# Carte_Logique_V1.net
KiCad netlist of a schematic drawn in EasyEDA
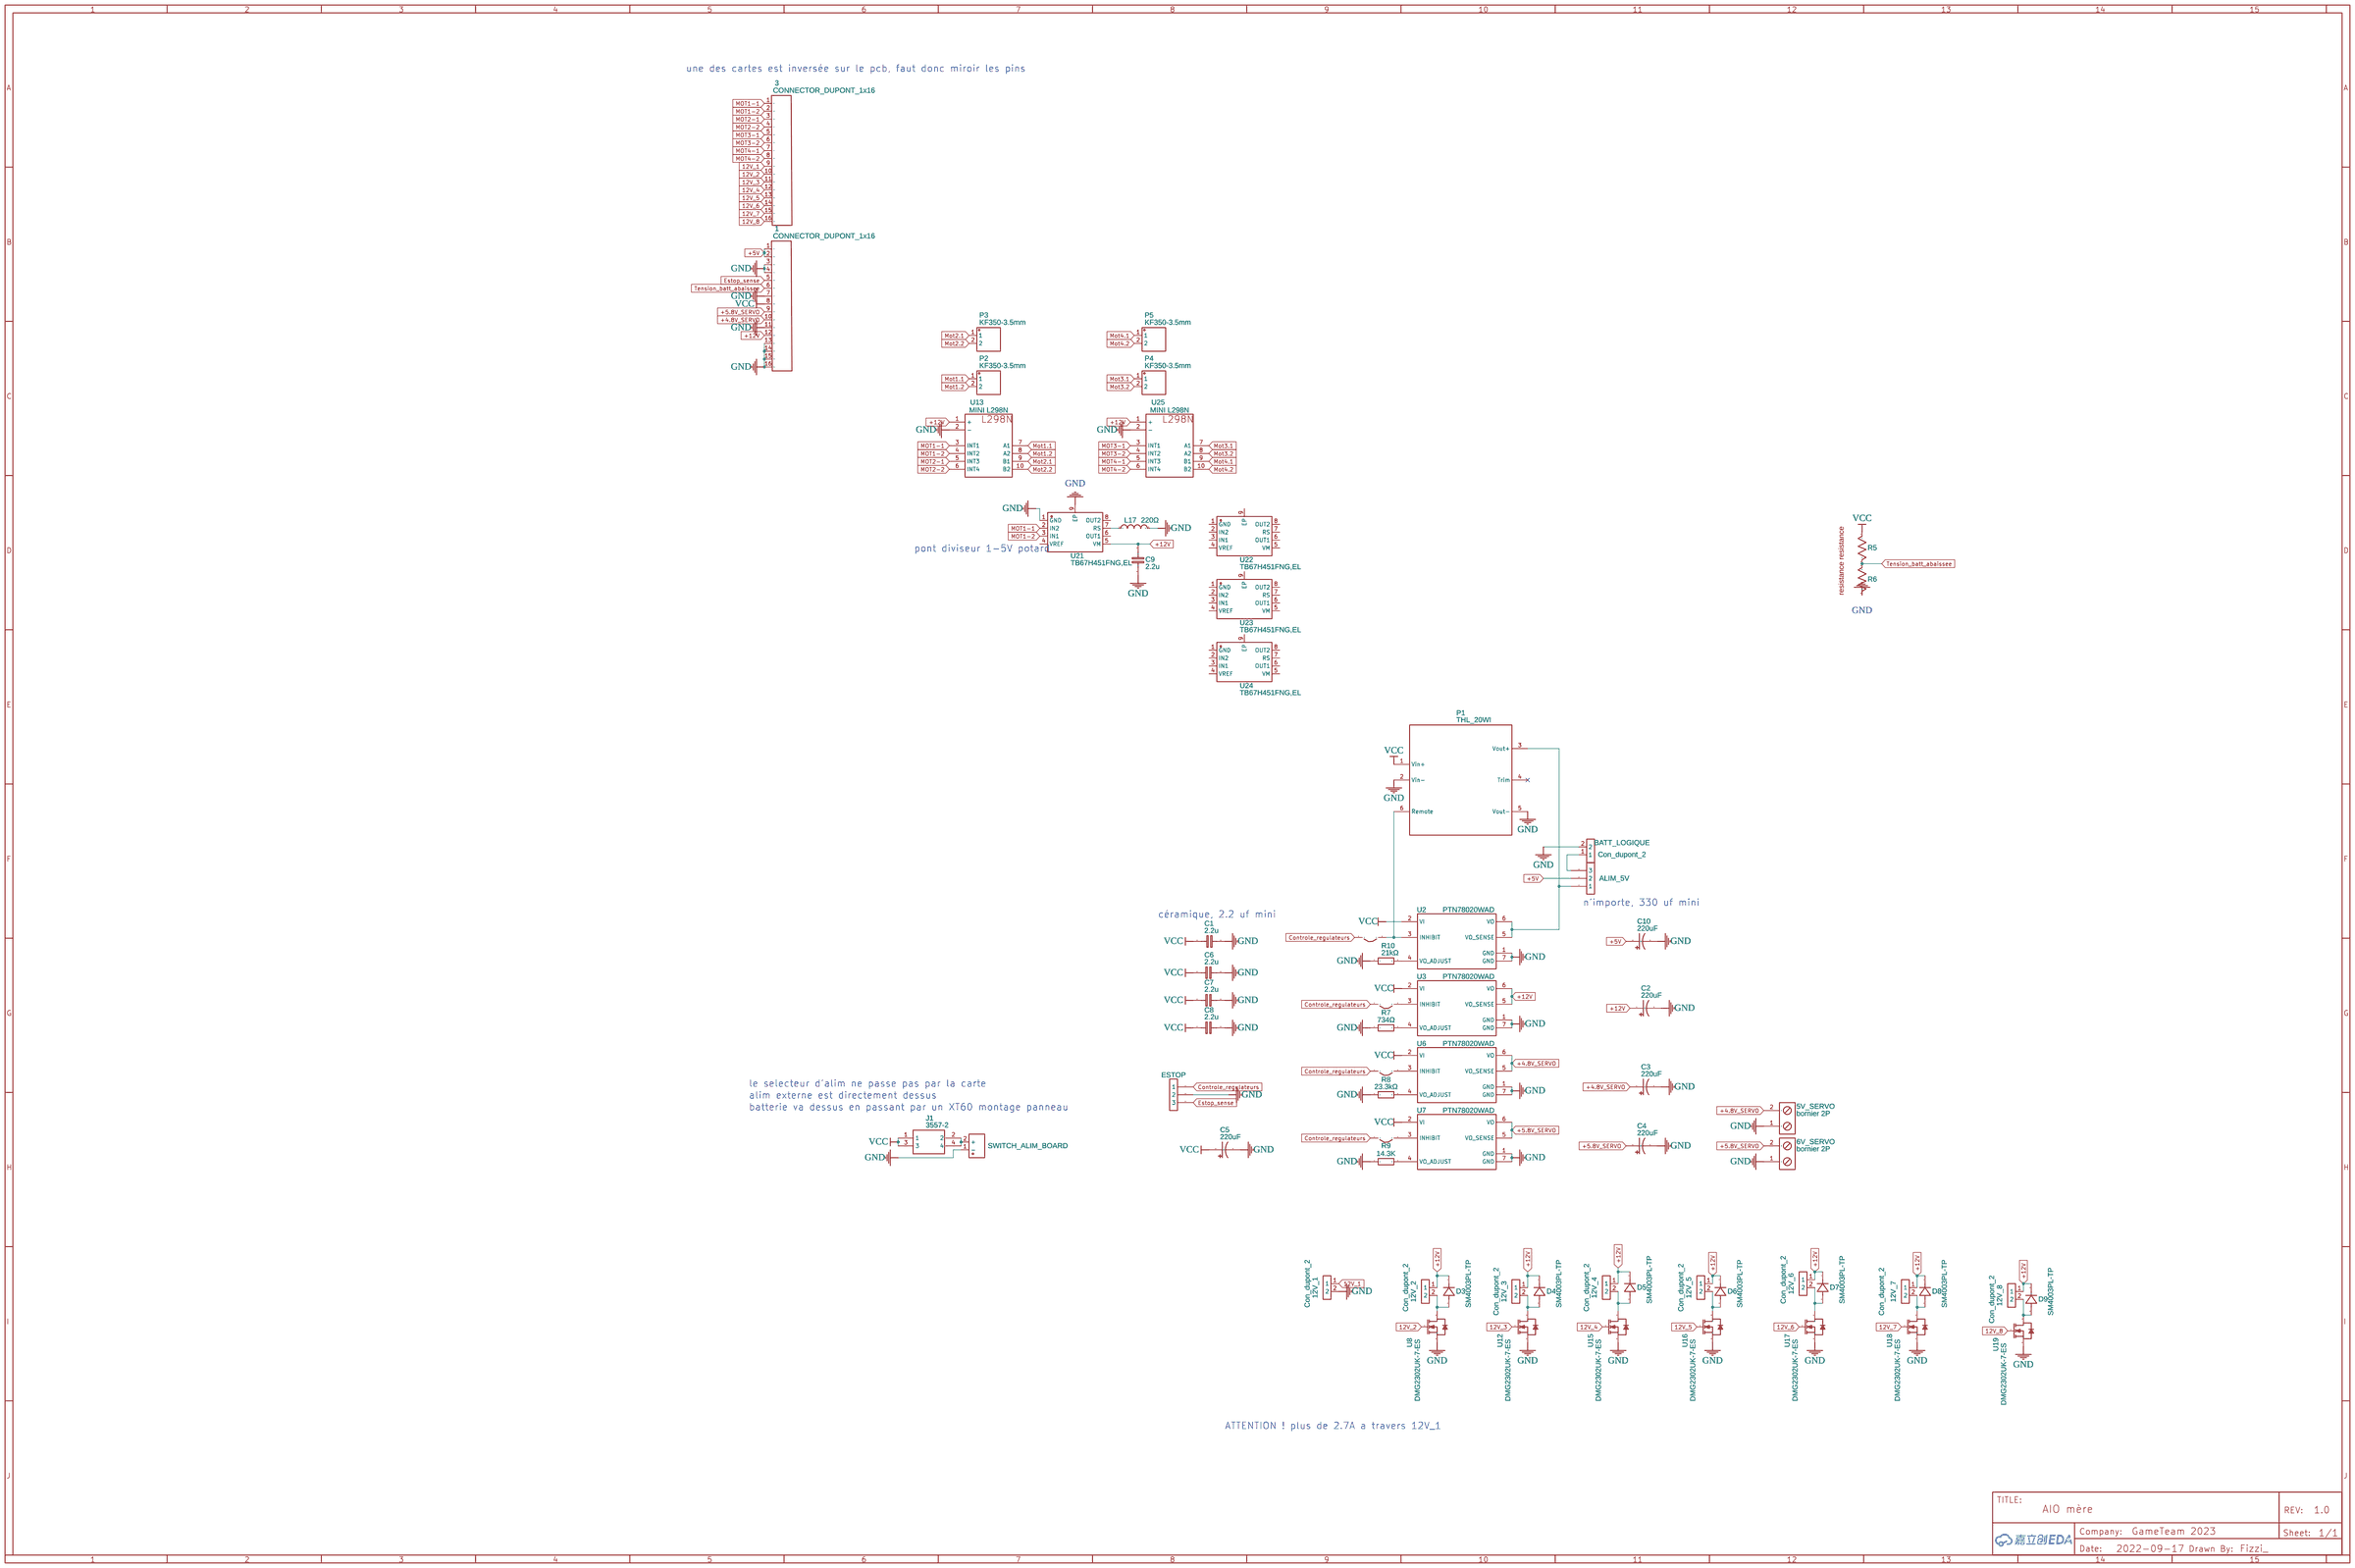
[diagram p0: schematic sheet]

(export (version "E")
  (design (tool "Eeschema 10.0.6"))
  (components
    (comp (ref "1") (value "CONNECTOR_DUPONT_1x16") (libsource (lib "") (part "CONNECTOR_DUPONT_1x16")))
    (comp (ref "3") (value "CONNECTOR_DUPONT_1x16") (libsource (lib "") (part "CONNECTOR_DUPONT_1x16")))
    (comp (ref "5V_SERVO")
      (value "bornier 2P")
      (fields (field (name "BOM_Manufacturer Part") "bornier"))
      (libsource (lib "") (part "bornier 2P"))
    )
    (comp (ref "6V_SERVO")
      (value "bornier 2P")
      (fields (field (name "BOM_Manufacturer Part") "bornier"))
      (libsource (lib "") (part "bornier 2P_1"))
    )
    (comp (ref "12V_1") (value "Con_dupont_2") (libsource (lib "") (part "Con_dupont_2")))
    (comp (ref "12V_2") (value "Con_dupont_2") (libsource (lib "") (part "Con_dupont_2")))
    (comp (ref "12V_3") (value "Con_dupont_2") (libsource (lib "") (part "Con_dupont_2")))
    (comp (ref "12V_4") (value "Con_dupont_2") (libsource (lib "") (part "Con_dupont_2")))
    (comp (ref "12V_5") (value "Con_dupont_2") (libsource (lib "") (part "Con_dupont_2")))
    (comp (ref "12V_6") (value "Con_dupont_2") (libsource (lib "") (part "Con_dupont_2")))
    (comp (ref "12V_7") (value "Con_dupont_2") (libsource (lib "") (part "Con_dupont_2")))
    (comp (ref "12V_8") (value "Con_dupont_2") (libsource (lib "") (part "Con_dupont_2")))
    (comp (ref "ALIM_5V") (value "Dupont 3Pin") (libsource (lib "") (part "Dupont 3Pin_1")))
    (comp (ref "BATT_LOGIQUE") (value "Con_dupont_2") (libsource (lib "") (part "Con_dupont_2_1")))
    (comp (ref "C1") (value "2.2u") (libsource (lib "") (part "C_0805_EU_2")))
    (comp (ref "C2")
      (value "220uF")
      (fields
        (field (name "BOM_Manufacturer Part") "EEEFK1H221P")
        (field (name "BOM_Supplier Part") "C178549")
      )
      (libsource (lib "") (part "EEEFK1H221P"))
    )
    (comp (ref "C3")
      (value "220uF")
      (fields
        (field (name "BOM_Manufacturer Part") "EEEFK1H221P")
        (field (name "BOM_Supplier Part") "C178549")
      )
      (libsource (lib "") (part "EEEFK1H221P"))
    )
    (comp (ref "C4")
      (value "220uF")
      (fields
        (field (name "BOM_Manufacturer Part") "EEEFK1H221P")
        (field (name "BOM_Supplier Part") "C178549")
      )
      (libsource (lib "") (part "EEEFK1H221P"))
    )
    (comp (ref "C5")
      (value "220uF")
      (fields
        (field (name "BOM_Manufacturer Part") "EEEFK1H221P")
        (field (name "BOM_Supplier Part") "C178549")
      )
      (libsource (lib "") (part "EEEFK1H221P"))
    )
    (comp (ref "C6") (value "2.2u") (libsource (lib "") (part "C_0805_EU")))
    (comp (ref "C7") (value "2.2u") (libsource (lib "") (part "C_0805_EU")))
    (comp (ref "C8") (value "2.2u") (libsource (lib "") (part "C_0805_EU")))
    (comp (ref "C9") (value "2.2u") (libsource (lib "") (part "C_0805_EU_1")))
    (comp (ref "C10")
      (value "220uF")
      (fields
        (field (name "BOM_Manufacturer Part") "EEEFK1H221P")
        (field (name "BOM_Supplier Part") "C178549")
      )
      (libsource (lib "") (part "EEEFK1H221P"))
    )
    (comp (ref "D3")
      (value "SM4003PL-TP")
      (fields (field (name "BOM_Supplier Part") "C725472"))
      (libsource (lib "") (part "SM4003PL-TP"))
    )
    (comp (ref "D4")
      (value "SM4003PL-TP")
      (fields (field (name "BOM_Supplier Part") "C725472"))
      (libsource (lib "") (part "SM4003PL-TP"))
    )
    (comp (ref "D5")
      (value "SM4003PL-TP")
      (fields (field (name "BOM_Supplier Part") "C725472"))
      (libsource (lib "") (part "SM4003PL-TP"))
    )
    (comp (ref "D6")
      (value "SM4003PL-TP")
      (fields (field (name "BOM_Supplier Part") "C725472"))
      (libsource (lib "") (part "SM4003PL-TP"))
    )
    (comp (ref "D7")
      (value "SM4003PL-TP")
      (fields (field (name "BOM_Supplier Part") "C725472"))
      (libsource (lib "") (part "SM4003PL-TP"))
    )
    (comp (ref "D8")
      (value "SM4003PL-TP")
      (fields (field (name "BOM_Supplier Part") "C725472"))
      (libsource (lib "") (part "SM4003PL-TP"))
    )
    (comp (ref "D9")
      (value "SM4003PL-TP")
      (fields (field (name "BOM_Supplier Part") "C725472"))
      (libsource (lib "") (part "SM4003PL-TP"))
    )
    (comp (ref "ESTOP") (value "Dupont 3Pin") (libsource (lib "") (part "Dupont 3Pin")))
    (comp (ref "J1") (value "3557-2") (libsource (lib "") (part "3557-2")))
    (comp (ref "JP8") (value "Jumper") (libsource (lib "") (part "Jumper Solder Bridge")))
    (comp (ref "JP9") (value "Jumper") (libsource (lib "") (part "Jumper Solder Bridge")))
    (comp (ref "JP10") (value "Jumper") (libsource (lib "") (part "Jumper Solder Bridge")))
    (comp (ref "JP11") (value "Jumper") (libsource (lib "") (part "Jumper Solder Bridge")))
    (comp (ref "L17")
      (value "220Ω")
      (fields
        (field (name "BOM_Manufacturer Part") "BLM18SG221TN1D")
        (field (name "BOM_Supplier Part") "C88988")
      )
      (libsource (lib "") (part "BLM18SG221TN1D"))
    )
    (comp (ref "P1") (value "THL_20WI") (libsource (lib "") (part "THL_20WI")))
    (comp (ref "P2")
      (value "KF350-3.5mm")
      (fields
        (field (name "BOM_Manufacturer Part") "WJ2EDGVC-5.08-2P")
        (field (name "BOM_Supplier Part") "C8445")
      )
      (libsource (lib "") (part "KF350-3.5mm"))
    )
    (comp (ref "P3")
      (value "KF350-3.5mm")
      (fields
        (field (name "BOM_Manufacturer Part") "WJ2EDGVC-5.08-2P")
        (field (name "BOM_Supplier Part") "C8445")
      )
      (libsource (lib "") (part "KF350-3.5mm"))
    )
    (comp (ref "P4")
      (value "KF350-3.5mm")
      (fields
        (field (name "BOM_Manufacturer Part") "WJ2EDGVC-5.08-2P")
        (field (name "BOM_Supplier Part") "C8445")
      )
      (libsource (lib "") (part "KF350-3.5mm"))
    )
    (comp (ref "P5")
      (value "KF350-3.5mm")
      (fields
        (field (name "BOM_Manufacturer Part") "WJ2EDGVC-5.08-2P")
        (field (name "BOM_Supplier Part") "C8445")
      )
      (libsource (lib "") (part "KF350-3.5mm"))
    )
    (comp (ref "R5") (value "1K") (libsource (lib "") (part "TROUGH HOLE RESISTOR 12MM")))
    (comp (ref "R6") (value "1K") (libsource (lib "") (part "TROUGH HOLE RESISTOR 12MM_1")))
    (comp (ref "R7")
      (value "734Ω")
      (fields
        (field (name "BOM_Manufacturer Part") "TR0603D383KP0515")
        (field (name "BOM_Supplier Part") "C153382")
      )
      (libsource (lib "") (part "TR0603D383KP0515"))
    )
    (comp (ref "R8")
      (value "23.3kΩ")
      (fields
        (field (name "BOM_Manufacturer Part") "0603WAF2322T5E")
        (field (name "BOM_Supplier Part") "C23346")
      )
      (libsource (lib "") (part "0603WAF2322T5E"))
    )
    (comp (ref "R9")
      (value "14.3K")
      (fields
        (field (name "BOM_Manufacturer Part") "AC0603FR-0714K3L")
        (field (name "BOM_Supplier Part") "C227592")
      )
      (libsource (lib "") (part "AC0603FR-0714K3L"))
    )
    (comp (ref "R10")
      (value "21kΩ")
      (fields
        (field (name "BOM_Manufacturer Part") "HPCR0603F21K0K9")
        (field (name "BOM_Supplier Part") "C365119")
      )
      (libsource (lib "") (part "HPCR0603F21K0K9"))
    )
    (comp (ref "SWITCH_ALIM_BOARD")
      (value "XT60-M")
      (fields
        (field (name "BOM_Manufacturer Part") "XT60UPB-M")
        (field (name "BOM_Supplier Part") "C2918078")
      )
      (libsource (lib "") (part "XT60-M"))
    )
    (comp (ref "U2") (value "PTN78020WAD") (libsource (lib "") (part "PTN78020WAD")))
    (comp (ref "U3") (value "PTN78020WAD") (libsource (lib "") (part "PTN78020WAD")))
    (comp (ref "U6") (value "PTN78020WAD") (libsource (lib "") (part "PTN78020WAD")))
    (comp (ref "U7") (value "PTN78020WAD") (libsource (lib "") (part "PTN78020WAD")))
    (comp (ref "U8")
      (value "DMG2302UK-7-ES")
      (fields (field (name "BOM_Supplier Part") "C5224188"))
      (libsource (lib "") (part "DMG2302UK-7-ES"))
    )
    (comp (ref "U12")
      (value "DMG2302UK-7-ES")
      (fields (field (name "BOM_Supplier Part") "C5224188"))
      (libsource (lib "") (part "DMG2302UK-7-ES"))
    )
    (comp (ref "U13") (value "MINI L298N") (libsource (lib "") (part "MINI L298N")))
    (comp (ref "U15")
      (value "DMG2302UK-7-ES")
      (fields (field (name "BOM_Supplier Part") "C5224188"))
      (libsource (lib "") (part "DMG2302UK-7-ES"))
    )
    (comp (ref "U16")
      (value "DMG2302UK-7-ES")
      (fields (field (name "BOM_Supplier Part") "C5224188"))
      (libsource (lib "") (part "DMG2302UK-7-ES"))
    )
    (comp (ref "U17")
      (value "DMG2302UK-7-ES")
      (fields (field (name "BOM_Supplier Part") "C5224188"))
      (libsource (lib "") (part "DMG2302UK-7-ES"))
    )
    (comp (ref "U18")
      (value "DMG2302UK-7-ES")
      (fields (field (name "BOM_Supplier Part") "C5224188"))
      (libsource (lib "") (part "DMG2302UK-7-ES"))
    )
    (comp (ref "U19")
      (value "DMG2302UK-7-ES")
      (fields (field (name "BOM_Supplier Part") "C5224188"))
      (libsource (lib "") (part "DMG2302UK-7-ES"))
    )
    (comp (ref "U21")
      (value "TB67H451FNG,EL")
      (fields (field (name "BOM_Supplier Part") "C1858375"))
      (libsource (lib "") (part "TB67H451FNG,EL"))
    )
    (comp (ref "U22")
      (value "TB67H451FNG,EL")
      (fields (field (name "BOM_Supplier Part") "C1858375"))
      (libsource (lib "") (part "TB67H451FNG,EL"))
    )
    (comp (ref "U23")
      (value "TB67H451FNG,EL")
      (fields (field (name "BOM_Supplier Part") "C1858375"))
      (libsource (lib "") (part "TB67H451FNG,EL"))
    )
    (comp (ref "U24")
      (value "TB67H451FNG,EL")
      (fields (field (name "BOM_Supplier Part") "C1858375"))
      (libsource (lib "") (part "TB67H451FNG,EL"))
    )
    (comp (ref "U25") (value "MINI L298N") (libsource (lib "") (part "MINI L298N")))
  )
  (nets
    (net (code "1") (name "+4.8V_SERVO") (class "Default")
      (node (ref "1") (pin "10") (pinfunction "10_10") (pintype "bidirectional"))
      (node (ref "5V_SERVO") (pin "2") (pinfunction "2_2") (pintype "unspecified"))
      (node (ref "C3") (pin "1") (pinfunction "1_1") (pintype "unspecified"))
      (node (ref "U6") (pin "5") (pinfunction "VO_SENSE_5") (pintype "unspecified"))
      (node (ref "U6") (pin "6") (pinfunction "VO_6") (pintype "passive"))
    )
    (net (code "2") (name "+5.8V_SERVO") (class "Default")
      (node (ref "1") (pin "9") (pinfunction "9_9") (pintype "bidirectional"))
      (node (ref "6V_SERVO") (pin "2") (pinfunction "2_2") (pintype "unspecified"))
      (node (ref "C4") (pin "1") (pinfunction "1_1") (pintype "unspecified"))
      (node (ref "U7") (pin "5") (pinfunction "VO_SENSE_5") (pintype "unspecified"))
      (node (ref "U7") (pin "6") (pinfunction "VO_6") (pintype "passive"))
    )
    (net (code "3") (name "+5V") (class "Default")
      (node (ref "1") (pin "1") (pinfunction "1_1") (pintype "bidirectional"))
      (node (ref "1") (pin "2") (pinfunction "2_2") (pintype "bidirectional"))
      (node (ref "ALIM_5V") (pin "2") (pinfunction "2_2") (pintype "unspecified"))
      (node (ref "C10") (pin "1") (pinfunction "1_1") (pintype "unspecified"))
    )
    (net (code "4") (name "+12V") (class "Default")
      (node (ref "1") (pin "12") (pinfunction "12_12") (pintype "bidirectional"))
      (node (ref "12V_2") (pin "1") (pinfunction "1_1") (pintype "unspecified"))
      (node (ref "12V_3") (pin "1") (pinfunction "1_1") (pintype "unspecified"))
      (node (ref "12V_4") (pin "1") (pinfunction "1_1") (pintype "unspecified"))
      (node (ref "12V_5") (pin "1") (pinfunction "1_1") (pintype "unspecified"))
      (node (ref "12V_6") (pin "1") (pinfunction "1_1") (pintype "unspecified"))
      (node (ref "12V_7") (pin "1") (pinfunction "1_1") (pintype "unspecified"))
      (node (ref "12V_8") (pin "1") (pinfunction "1_1") (pintype "unspecified"))
      (node (ref "C2") (pin "1") (pinfunction "1_1") (pintype "unspecified"))
      (node (ref "C9") (pin "2") (pinfunction "2_2") (pintype "unspecified"))
      (node (ref "D3") (pin "1") (pinfunction "K_1") (pintype "unspecified"))
      (node (ref "D4") (pin "1") (pinfunction "K_1") (pintype "unspecified"))
      (node (ref "D5") (pin "1") (pinfunction "K_1") (pintype "unspecified"))
      (node (ref "D6") (pin "1") (pinfunction "K_1") (pintype "unspecified"))
      (node (ref "D7") (pin "1") (pinfunction "K_1") (pintype "unspecified"))
      (node (ref "D8") (pin "1") (pinfunction "K_1") (pintype "unspecified"))
      (node (ref "D9") (pin "1") (pinfunction "K_1") (pintype "unspecified"))
      (node (ref "U13") (pin "1") (pinfunction "+_1") (pintype "unspecified"))
      (node (ref "U21") (pin "5") (pinfunction "VM_5") (pintype "unspecified"))
      (node (ref "U25") (pin "1") (pinfunction "+_1") (pintype "unspecified"))
      (node (ref "U3") (pin "5") (pinfunction "VO_SENSE_5") (pintype "unspecified"))
      (node (ref "U3") (pin "6") (pinfunction "VO_6") (pintype "passive"))
    )
    (net (code "5") (name "12V_1") (class "Default")
      (node (ref "12V_1") (pin "1") (pinfunction "1_1") (pintype "unspecified"))
      (node (ref "3") (pin "9") (pinfunction "9_9") (pintype "bidirectional"))
    )
    (net (code "6") (name "12V_2") (class "Default")
      (node (ref "3") (pin "10") (pinfunction "10_10") (pintype "bidirectional"))
      (node (ref "U8") (pin "1") (pinfunction "G_1") (pintype "unspecified"))
    )
    (net (code "7") (name "12V_3") (class "Default")
      (node (ref "3") (pin "11") (pinfunction "11_11") (pintype "bidirectional"))
      (node (ref "U12") (pin "1") (pinfunction "G_1") (pintype "unspecified"))
    )
    (net (code "8") (name "12V_4") (class "Default")
      (node (ref "3") (pin "12") (pinfunction "12_12") (pintype "bidirectional"))
      (node (ref "U15") (pin "1") (pinfunction "G_1") (pintype "unspecified"))
    )
    (net (code "9") (name "12V_5") (class "Default")
      (node (ref "3") (pin "13") (pinfunction "13_13") (pintype "bidirectional"))
      (node (ref "U16") (pin "1") (pinfunction "G_1") (pintype "unspecified"))
    )
    (net (code "10") (name "12V_6") (class "Default")
      (node (ref "3") (pin "14") (pinfunction "14_14") (pintype "bidirectional"))
      (node (ref "U17") (pin "1") (pinfunction "G_1") (pintype "unspecified"))
    )
    (net (code "11") (name "12V_7") (class "Default")
      (node (ref "3") (pin "15") (pinfunction "15_15") (pintype "bidirectional"))
      (node (ref "U18") (pin "1") (pinfunction "G_1") (pintype "unspecified"))
    )
    (net (code "12") (name "12V_8") (class "Default")
      (node (ref "3") (pin "16") (pinfunction "16_16") (pintype "bidirectional"))
      (node (ref "U19") (pin "1") (pinfunction "G_1") (pintype "unspecified"))
    )
    (net (code "13") (name "Controle_regulateurs") (class "Default")
      (node (ref "ESTOP") (pin "1") (pinfunction "1_1") (pintype "unspecified"))
      (node (ref "JP10") (pin "1") (pinfunction "1_1") (pintype "input"))
      (node (ref "JP11") (pin "1") (pinfunction "1_1") (pintype "input"))
      (node (ref "JP8") (pin "1") (pinfunction "1_1") (pintype "input"))
      (node (ref "JP9") (pin "1") (pinfunction "1_1") (pintype "input"))
    )
    (net (code "14") (name "Estop_sense") (class "Default")
      (node (ref "1") (pin "5") (pinfunction "5_5") (pintype "bidirectional"))
      (node (ref "ESTOP") (pin "3") (pinfunction "3_3") (pintype "unspecified"))
    )
    (net (code "15") (name "GND") (class "Default")
      (node (ref "1") (pin "11") (pinfunction "11_11") (pintype "bidirectional"))
      (node (ref "1") (pin "13") (pinfunction "13_13") (pintype "bidirectional"))
      (node (ref "1") (pin "14") (pinfunction "14_14") (pintype "bidirectional"))
      (node (ref "1") (pin "15") (pinfunction "15_15") (pintype "bidirectional"))
      (node (ref "1") (pin "16") (pinfunction "16_16") (pintype "bidirectional"))
      (node (ref "1") (pin "3") (pinfunction "3_3") (pintype "bidirectional"))
      (node (ref "1") (pin "4") (pinfunction "4_4") (pintype "bidirectional"))
      (node (ref "1") (pin "7") (pinfunction "7_7") (pintype "bidirectional"))
      (node (ref "12V_1") (pin "2") (pinfunction "2_2") (pintype "unspecified"))
      (node (ref "5V_SERVO") (pin "1") (pinfunction "1_1") (pintype "unspecified"))
      (node (ref "6V_SERVO") (pin "1") (pinfunction "1_1") (pintype "unspecified"))
      (node (ref "BATT_LOGIQUE") (pin "2") (pinfunction "2_2") (pintype "unspecified"))
      (node (ref "C1") (pin "1") (pinfunction "1_1") (pintype "unspecified"))
      (node (ref "C10") (pin "2") (pinfunction "2_2") (pintype "unspecified"))
      (node (ref "C2") (pin "2") (pinfunction "2_2") (pintype "unspecified"))
      (node (ref "C3") (pin "2") (pinfunction "2_2") (pintype "unspecified"))
      (node (ref "C4") (pin "2") (pinfunction "2_2") (pintype "unspecified"))
      (node (ref "C5") (pin "2") (pinfunction "2_2") (pintype "unspecified"))
      (node (ref "C6") (pin "2") (pinfunction "2_2") (pintype "unspecified"))
      (node (ref "C7") (pin "2") (pinfunction "2_2") (pintype "unspecified"))
      (node (ref "C8") (pin "2") (pinfunction "2_2") (pintype "unspecified"))
      (node (ref "C9") (pin "1") (pinfunction "1_1") (pintype "unspecified"))
      (node (ref "ESTOP") (pin "2") (pinfunction "2_2") (pintype "unspecified"))
      (node (ref "L17") (pin "2") (pinfunction "2_2") (pintype "unspecified"))
      (node (ref "P1") (pin "2") (pinfunction "Vin-_2") (pintype "unspecified"))
      (node (ref "P1") (pin "5") (pinfunction "Vout-_5") (pintype "unspecified"))
      (node (ref "R10") (pin "1") (pinfunction "1_1") (pintype "unspecified"))
      (node (ref "R6") (pin "2") (pinfunction "2_2") (pintype "unspecified"))
      (node (ref "R7") (pin "1") (pinfunction "1_1") (pintype "unspecified"))
      (node (ref "R8") (pin "1") (pinfunction "1_1") (pintype "input"))
      (node (ref "R9") (pin "1") (pinfunction "1_1") (pintype "unspecified"))
      (node (ref "SWITCH_ALIM_BOARD") (pin "1") (pinfunction "-_1") (pintype "unspecified"))
      (node (ref "U12") (pin "2") (pinfunction "S_2") (pintype "unspecified"))
      (node (ref "U13") (pin "2") (pinfunction "-_2") (pintype "unspecified"))
      (node (ref "U15") (pin "2") (pinfunction "S_2") (pintype "unspecified"))
      (node (ref "U16") (pin "2") (pinfunction "S_2") (pintype "unspecified"))
      (node (ref "U17") (pin "2") (pinfunction "S_2") (pintype "unspecified"))
      (node (ref "U18") (pin "2") (pinfunction "S_2") (pintype "unspecified"))
      (node (ref "U19") (pin "2") (pinfunction "S_2") (pintype "unspecified"))
      (node (ref "U2") (pin "1") (pinfunction "GND_1") (pintype "passive"))
      (node (ref "U2") (pin "7") (pinfunction "GND_7") (pintype "passive"))
      (node (ref "U21") (pin "1") (pinfunction "GND_1") (pintype "unspecified"))
      (node (ref "U21") (pin "9") (pinfunction "EP_9") (pintype "unspecified"))
      (node (ref "U25") (pin "2") (pinfunction "-_2") (pintype "unspecified"))
      (node (ref "U3") (pin "1") (pinfunction "GND_1") (pintype "passive"))
      (node (ref "U3") (pin "7") (pinfunction "GND_7") (pintype "passive"))
      (node (ref "U6") (pin "1") (pinfunction "GND_1") (pintype "passive"))
      (node (ref "U6") (pin "7") (pinfunction "GND_7") (pintype "passive"))
      (node (ref "U7") (pin "1") (pinfunction "GND_1") (pintype "passive"))
      (node (ref "U7") (pin "7") (pinfunction "GND_7") (pintype "passive"))
      (node (ref "U8") (pin "2") (pinfunction "S_2") (pintype "unspecified"))
    )
    (net (code "16") (name "MOT1-1") (class "Default")
      (node (ref "3") (pin "1") (pinfunction "1_1") (pintype "bidirectional"))
      (node (ref "U13") (pin "3") (pinfunction "INT1_3") (pintype "unspecified"))
      (node (ref "U21") (pin "2") (pinfunction "IN2_2") (pintype "unspecified"))
    )
    (net (code "17") (name "MOT1-2") (class "Default")
      (node (ref "3") (pin "2") (pinfunction "2_2") (pintype "bidirectional"))
      (node (ref "U13") (pin "4") (pinfunction "INT2_4") (pintype "unspecified"))
      (node (ref "U21") (pin "3") (pinfunction "IN1_3") (pintype "unspecified"))
    )
    (net (code "18") (name "MOT2-1") (class "Default")
      (node (ref "3") (pin "3") (pinfunction "3_3") (pintype "bidirectional"))
      (node (ref "U13") (pin "5") (pinfunction "INT3_5") (pintype "unspecified"))
    )
    (net (code "19") (name "MOT2-2") (class "Default")
      (node (ref "3") (pin "4") (pinfunction "4_4") (pintype "bidirectional"))
      (node (ref "U13") (pin "6") (pinfunction "INT4_6") (pintype "unspecified"))
    )
    (net (code "20") (name "MOT3-1") (class "Default")
      (node (ref "3") (pin "5") (pinfunction "5_5") (pintype "bidirectional"))
      (node (ref "U25") (pin "3") (pinfunction "INT1_3") (pintype "unspecified"))
    )
    (net (code "21") (name "MOT3-2") (class "Default")
      (node (ref "3") (pin "6") (pinfunction "6_6") (pintype "bidirectional"))
      (node (ref "U25") (pin "4") (pinfunction "INT2_4") (pintype "unspecified"))
    )
    (net (code "22") (name "MOT4-1") (class "Default")
      (node (ref "3") (pin "7") (pinfunction "7_7") (pintype "bidirectional"))
      (node (ref "U25") (pin "5") (pinfunction "INT3_5") (pintype "unspecified"))
    )
    (net (code "23") (name "MOT4-2") (class "Default")
      (node (ref "3") (pin "8") (pinfunction "8_8") (pintype "bidirectional"))
      (node (ref "U25") (pin "6") (pinfunction "INT4_6") (pintype "unspecified"))
    )
    (net (code "24") (name "Mot1.1") (class "Default")
      (node (ref "P2") (pin "1") (pinfunction "1_1") (pintype "unspecified"))
      (node (ref "U13") (pin "7") (pinfunction "A1_7") (pintype "unspecified"))
    )
    (net (code "25") (name "Mot1.2") (class "Default")
      (node (ref "P2") (pin "2") (pinfunction "2_2") (pintype "unspecified"))
      (node (ref "U13") (pin "8") (pinfunction "A2_8") (pintype "unspecified"))
    )
    (net (code "26") (name "Mot2.1") (class "Default")
      (node (ref "P3") (pin "1") (pinfunction "1_1") (pintype "unspecified"))
      (node (ref "U13") (pin "9") (pinfunction "B1_9") (pintype "unspecified"))
    )
    (net (code "27") (name "Mot2.2") (class "Default")
      (node (ref "P3") (pin "2") (pinfunction "2_2") (pintype "unspecified"))
      (node (ref "U13") (pin "10") (pinfunction "B2_10") (pintype "unspecified"))
    )
    (net (code "28") (name "Mot3.1") (class "Default")
      (node (ref "P4") (pin "1") (pinfunction "1_1") (pintype "unspecified"))
      (node (ref "U25") (pin "7") (pinfunction "A1_7") (pintype "unspecified"))
    )
    (net (code "29") (name "Mot3.2") (class "Default")
      (node (ref "P4") (pin "2") (pinfunction "2_2") (pintype "unspecified"))
      (node (ref "U25") (pin "8") (pinfunction "A2_8") (pintype "unspecified"))
    )
    (net (code "30") (name "Mot4.1") (class "Default")
      (node (ref "P5") (pin "1") (pinfunction "1_1") (pintype "unspecified"))
      (node (ref "U25") (pin "9") (pinfunction "B1_9") (pintype "unspecified"))
    )
    (net (code "31") (name "Mot4.2") (class "Default")
      (node (ref "P5") (pin "2") (pinfunction "2_2") (pintype "unspecified"))
      (node (ref "U25") (pin "10") (pinfunction "B2_10") (pintype "unspecified"))
    )
    (net (code "32") (name "Net-(ALIM_5V-Pad3)") (class "Default")
      (node (ref "ALIM_5V") (pin "3") (pinfunction "3_3") (pintype "unspecified"))
      (node (ref "BATT_LOGIQUE") (pin "1") (pinfunction "1_1") (pintype "unspecified"))
    )
    (net (code "33") (name "Net-(D3-A)") (class "Default")
      (node (ref "12V_2") (pin "2") (pinfunction "2_2") (pintype "unspecified"))
      (node (ref "D3") (pin "2") (pinfunction "A_2") (pintype "unspecified"))
      (node (ref "U8") (pin "3") (pinfunction "D_3") (pintype "unspecified"))
    )
    (net (code "34") (name "Net-(D4-A)") (class "Default")
      (node (ref "12V_3") (pin "2") (pinfunction "2_2") (pintype "unspecified"))
      (node (ref "D4") (pin "2") (pinfunction "A_2") (pintype "unspecified"))
      (node (ref "U12") (pin "3") (pinfunction "D_3") (pintype "unspecified"))
    )
    (net (code "35") (name "Net-(D5-A)") (class "Default")
      (node (ref "12V_4") (pin "2") (pinfunction "2_2") (pintype "unspecified"))
      (node (ref "D5") (pin "2") (pinfunction "A_2") (pintype "unspecified"))
      (node (ref "U15") (pin "3") (pinfunction "D_3") (pintype "unspecified"))
    )
    (net (code "36") (name "Net-(D6-A)") (class "Default")
      (node (ref "12V_5") (pin "2") (pinfunction "2_2") (pintype "unspecified"))
      (node (ref "D6") (pin "2") (pinfunction "A_2") (pintype "unspecified"))
      (node (ref "U16") (pin "3") (pinfunction "D_3") (pintype "unspecified"))
    )
    (net (code "37") (name "Net-(D7-A)") (class "Default")
      (node (ref "12V_6") (pin "2") (pinfunction "2_2") (pintype "unspecified"))
      (node (ref "D7") (pin "2") (pinfunction "A_2") (pintype "unspecified"))
      (node (ref "U17") (pin "3") (pinfunction "D_3") (pintype "unspecified"))
    )
    (net (code "38") (name "Net-(D8-A)") (class "Default")
      (node (ref "12V_7") (pin "2") (pinfunction "2_2") (pintype "unspecified"))
      (node (ref "D8") (pin "2") (pinfunction "A_2") (pintype "unspecified"))
      (node (ref "U18") (pin "3") (pinfunction "D_3") (pintype "unspecified"))
    )
    (net (code "39") (name "Net-(D9-A)") (class "Default")
      (node (ref "12V_8") (pin "2") (pinfunction "2_2") (pintype "unspecified"))
      (node (ref "D9") (pin "2") (pinfunction "A_2") (pintype "unspecified"))
      (node (ref "U19") (pin "3") (pinfunction "D_3") (pintype "unspecified"))
    )
    (net (code "40") (name "Net-(P1-Remote)") (class "Default")
      (node (ref "JP8") (pin "2") (pinfunction "2_2") (pintype "input"))
      (node (ref "P1") (pin "6") (pinfunction "Remote_6") (pintype "unspecified"))
      (node (ref "U2") (pin "3") (pinfunction "INHIBIT_3") (pintype "unspecified"))
    )
    (net (code "41") (name "Net-(P1-Vout+)") (class "Default")
      (node (ref "ALIM_5V") (pin "1") (pinfunction "1_1") (pintype "unspecified"))
      (node (ref "P1") (pin "3") (pinfunction "Vout+_3") (pintype "unspecified"))
      (node (ref "U2") (pin "5") (pinfunction "VO_SENSE_5") (pintype "unspecified"))
      (node (ref "U2") (pin "6") (pinfunction "VO_6") (pintype "passive"))
    )
    (net (code "42") (name "Net-(SWITCH_ALIM_BOARD-+)") (class "Default")
      (node (ref "J1") (pin "2") (pinfunction "2_2") (pintype "bidirectional"))
      (node (ref "J1") (pin "4") (pinfunction "4_4") (pintype "bidirectional"))
      (node (ref "SWITCH_ALIM_BOARD") (pin "2") (pinfunction "+_2") (pintype "unspecified"))
    )
    (net (code "43") (name "Net-(U2-VO_ADJUST)") (class "Default")
      (node (ref "R10") (pin "2") (pinfunction "2_2") (pintype "unspecified"))
      (node (ref "U2") (pin "4") (pinfunction "VO_ADJUST_4") (pintype "unspecified"))
    )
    (net (code "44") (name "Net-(U3-INHIBIT)") (class "Default")
      (node (ref "JP9") (pin "2") (pinfunction "2_2") (pintype "input"))
      (node (ref "U3") (pin "3") (pinfunction "INHIBIT_3") (pintype "unspecified"))
    )
    (net (code "45") (name "Net-(U3-VO_ADJUST)") (class "Default")
      (node (ref "R7") (pin "2") (pinfunction "2_2") (pintype "unspecified"))
      (node (ref "U3") (pin "4") (pinfunction "VO_ADJUST_4") (pintype "unspecified"))
    )
    (net (code "46") (name "Net-(U6-INHIBIT)") (class "Default")
      (node (ref "JP10") (pin "2") (pinfunction "2_2") (pintype "input"))
      (node (ref "U6") (pin "3") (pinfunction "INHIBIT_3") (pintype "unspecified"))
    )
    (net (code "47") (name "Net-(U6-VO_ADJUST)") (class "Default")
      (node (ref "R8") (pin "2") (pinfunction "2_2") (pintype "input"))
      (node (ref "U6") (pin "4") (pinfunction "VO_ADJUST_4") (pintype "unspecified"))
    )
    (net (code "48") (name "Net-(U7-INHIBIT)") (class "Default")
      (node (ref "JP11") (pin "2") (pinfunction "2_2") (pintype "input"))
      (node (ref "U7") (pin "3") (pinfunction "INHIBIT_3") (pintype "unspecified"))
    )
    (net (code "49") (name "Net-(U7-VO_ADJUST)") (class "Default")
      (node (ref "R9") (pin "2") (pinfunction "2_2") (pintype "unspecified"))
      (node (ref "U7") (pin "4") (pinfunction "VO_ADJUST_4") (pintype "unspecified"))
    )
    (net (code "50") (name "Net-(U21-RS)") (class "Default")
      (node (ref "L17") (pin "1") (pinfunction "1_1") (pintype "unspecified"))
      (node (ref "U21") (pin "7") (pinfunction "RS_7") (pintype "unspecified"))
    )
    (net (code "51") (name "Tension_batt_abaissee") (class "Default")
      (node (ref "1") (pin "6") (pinfunction "6_6") (pintype "bidirectional"))
      (node (ref "R5") (pin "2") (pinfunction "2_2") (pintype "unspecified"))
      (node (ref "R6") (pin "1") (pinfunction "1_1") (pintype "unspecified"))
    )
    (net (code "52") (name "VCC") (class "Default")
      (node (ref "1") (pin "8") (pinfunction "8_8") (pintype "bidirectional"))
      (node (ref "C1") (pin "2") (pinfunction "2_2") (pintype "unspecified"))
      (node (ref "C5") (pin "1") (pinfunction "1_1") (pintype "unspecified"))
      (node (ref "C6") (pin "1") (pinfunction "1_1") (pintype "unspecified"))
      (node (ref "C7") (pin "1") (pinfunction "1_1") (pintype "unspecified"))
      (node (ref "C8") (pin "1") (pinfunction "1_1") (pintype "unspecified"))
      (node (ref "J1") (pin "1") (pinfunction "1_1") (pintype "bidirectional"))
      (node (ref "J1") (pin "3") (pinfunction "3_3") (pintype "bidirectional"))
      (node (ref "P1") (pin "1") (pinfunction "Vin+_1") (pintype "unspecified"))
      (node (ref "R5") (pin "1") (pinfunction "1_1") (pintype "unspecified"))
      (node (ref "U2") (pin "2") (pinfunction "VI_2") (pintype "passive"))
      (node (ref "U3") (pin "2") (pinfunction "VI_2") (pintype "passive"))
      (node (ref "U6") (pin "2") (pinfunction "VI_2") (pintype "passive"))
      (node (ref "U7") (pin "2") (pinfunction "VI_2") (pintype "passive"))
    )
    (net (code "53") (name "unconnected-(P1-Trim-Pad4)") (class "Default")
      (node (ref "P1") (pin "4") (pinfunction "Trim_4") (pintype "unspecified+no_connect"))
    )
    (net (code "54") (name "unconnected-(U21-OUT1-Pad6)") (class "Default")
      (node (ref "U21") (pin "6") (pinfunction "OUT1_6") (pintype "unspecified"))
    )
    (net (code "55") (name "unconnected-(U21-OUT2-Pad8)") (class "Default")
      (node (ref "U21") (pin "8") (pinfunction "OUT2_8") (pintype "unspecified"))
    )
    (net (code "56") (name "unconnected-(U21-VREF-Pad4)") (class "Default")
      (node (ref "U21") (pin "4") (pinfunction "VREF_4") (pintype "unspecified"))
    )
    (net (code "57") (name "unconnected-(U22-EP-Pad9)") (class "Default")
      (node (ref "U22") (pin "9") (pinfunction "EP_9") (pintype "unspecified"))
    )
    (net (code "58") (name "unconnected-(U22-GND-Pad1)") (class "Default")
      (node (ref "U22") (pin "1") (pinfunction "GND_1") (pintype "unspecified"))
    )
    (net (code "59") (name "unconnected-(U22-IN1-Pad3)") (class "Default")
      (node (ref "U22") (pin "3") (pinfunction "IN1_3") (pintype "unspecified"))
    )
    (net (code "60") (name "unconnected-(U22-IN2-Pad2)") (class "Default")
      (node (ref "U22") (pin "2") (pinfunction "IN2_2") (pintype "unspecified"))
    )
    (net (code "61") (name "unconnected-(U22-OUT1-Pad6)") (class "Default")
      (node (ref "U22") (pin "6") (pinfunction "OUT1_6") (pintype "unspecified"))
    )
    (net (code "62") (name "unconnected-(U22-OUT2-Pad8)") (class "Default")
      (node (ref "U22") (pin "8") (pinfunction "OUT2_8") (pintype "unspecified"))
    )
    (net (code "63") (name "unconnected-(U22-RS-Pad7)") (class "Default")
      (node (ref "U22") (pin "7") (pinfunction "RS_7") (pintype "unspecified"))
    )
    (net (code "64") (name "unconnected-(U22-VM-Pad5)") (class "Default")
      (node (ref "U22") (pin "5") (pinfunction "VM_5") (pintype "unspecified"))
    )
    (net (code "65") (name "unconnected-(U22-VREF-Pad4)") (class "Default")
      (node (ref "U22") (pin "4") (pinfunction "VREF_4") (pintype "unspecified"))
    )
    (net (code "66") (name "unconnected-(U23-EP-Pad9)") (class "Default")
      (node (ref "U23") (pin "9") (pinfunction "EP_9") (pintype "unspecified"))
    )
    (net (code "67") (name "unconnected-(U23-GND-Pad1)") (class "Default")
      (node (ref "U23") (pin "1") (pinfunction "GND_1") (pintype "unspecified"))
    )
    (net (code "68") (name "unconnected-(U23-IN1-Pad3)") (class "Default")
      (node (ref "U23") (pin "3") (pinfunction "IN1_3") (pintype "unspecified"))
    )
    (net (code "69") (name "unconnected-(U23-IN2-Pad2)") (class "Default")
      (node (ref "U23") (pin "2") (pinfunction "IN2_2") (pintype "unspecified"))
    )
    (net (code "70") (name "unconnected-(U23-OUT1-Pad6)") (class "Default")
      (node (ref "U23") (pin "6") (pinfunction "OUT1_6") (pintype "unspecified"))
    )
    (net (code "71") (name "unconnected-(U23-OUT2-Pad8)") (class "Default")
      (node (ref "U23") (pin "8") (pinfunction "OUT2_8") (pintype "unspecified"))
    )
    (net (code "72") (name "unconnected-(U23-RS-Pad7)") (class "Default")
      (node (ref "U23") (pin "7") (pinfunction "RS_7") (pintype "unspecified"))
    )
    (net (code "73") (name "unconnected-(U23-VM-Pad5)") (class "Default")
      (node (ref "U23") (pin "5") (pinfunction "VM_5") (pintype "unspecified"))
    )
    (net (code "74") (name "unconnected-(U23-VREF-Pad4)") (class "Default")
      (node (ref "U23") (pin "4") (pinfunction "VREF_4") (pintype "unspecified"))
    )
    (net (code "75") (name "unconnected-(U24-EP-Pad9)") (class "Default")
      (node (ref "U24") (pin "9") (pinfunction "EP_9") (pintype "unspecified"))
    )
    (net (code "76") (name "unconnected-(U24-GND-Pad1)") (class "Default")
      (node (ref "U24") (pin "1") (pinfunction "GND_1") (pintype "unspecified"))
    )
    (net (code "77") (name "unconnected-(U24-IN1-Pad3)") (class "Default")
      (node (ref "U24") (pin "3") (pinfunction "IN1_3") (pintype "unspecified"))
    )
    (net (code "78") (name "unconnected-(U24-IN2-Pad2)") (class "Default")
      (node (ref "U24") (pin "2") (pinfunction "IN2_2") (pintype "unspecified"))
    )
    (net (code "79") (name "unconnected-(U24-OUT1-Pad6)") (class "Default")
      (node (ref "U24") (pin "6") (pinfunction "OUT1_6") (pintype "unspecified"))
    )
    (net (code "80") (name "unconnected-(U24-OUT2-Pad8)") (class "Default")
      (node (ref "U24") (pin "8") (pinfunction "OUT2_8") (pintype "unspecified"))
    )
    (net (code "81") (name "unconnected-(U24-RS-Pad7)") (class "Default")
      (node (ref "U24") (pin "7") (pinfunction "RS_7") (pintype "unspecified"))
    )
    (net (code "82") (name "unconnected-(U24-VM-Pad5)") (class "Default")
      (node (ref "U24") (pin "5") (pinfunction "VM_5") (pintype "unspecified"))
    )
    (net (code "83") (name "unconnected-(U24-VREF-Pad4)") (class "Default")
      (node (ref "U24") (pin "4") (pinfunction "VREF_4") (pintype "unspecified"))
    )
  )
)
